# circuitofinal.net
KiCad netlist of a schematic drawn in EAGLE
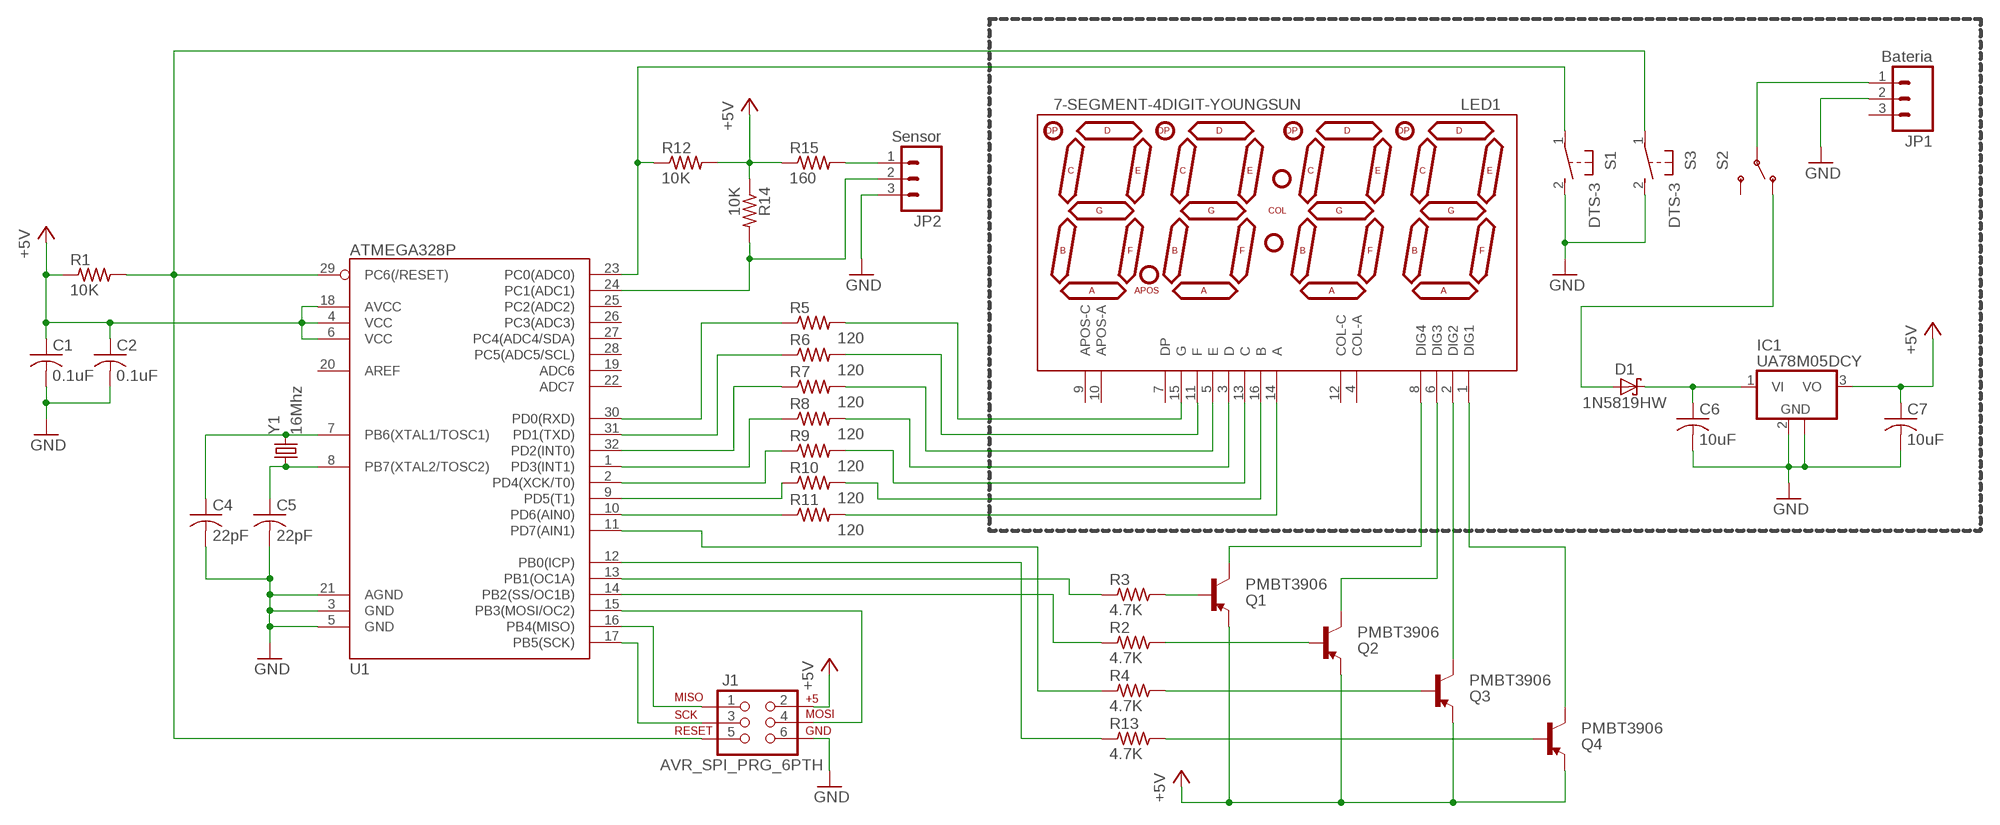
[diagram p0: schematic, sheet 1]

(export (version "E")
  (design (tool "Eeschema 10.0.6"))
  (components
    (comp (ref "C1")
      (value "0.1uF")
      (footprint "eagle-import:C0805")
      (libsource (lib "eagle-import") (part "C-USC0805"))
    )
    (comp (ref "C2")
      (value "0.1uF")
      (footprint "eagle-import:C0805")
      (libsource (lib "eagle-import") (part "C-USC0805"))
    )
    (comp (ref "C4")
      (value "22pF")
      (footprint "eagle-import:C1206")
      (libsource (lib "eagle-import") (part "C-USC1206"))
    )
    (comp (ref "C5")
      (value "22pF")
      (footprint "eagle-import:C1206")
      (libsource (lib "eagle-import") (part "C-USC1206"))
    )
    (comp (ref "C6")
      (value "10uF")
      (footprint "eagle-import:C1206")
      (libsource (lib "eagle-import") (part "C-USC1206"))
    )
    (comp (ref "C7")
      (value "10uF")
      (footprint "eagle-import:C1206")
      (libsource (lib "eagle-import") (part "C-USC1206"))
    )
    (comp (ref "D1")
      (value "1N5819HW")
      (footprint "eagle-import:SOD-123")
      (libsource (lib "eagle-import") (part "1N5819HW"))
    )
    (comp (ref "IC1")
      (value "UA78M05DCY")
      (footprint "eagle-import:SOT223")
      (libsource (lib "eagle-import") (part "UA78MDCY05"))
    )
    (comp (ref "J1")
      (value "AVR_SPI_PRG_6PTH")
      (footprint "eagle-import:2X3")
      (libsource (lib "eagle-import") (part "AVR_SPI_PRG_6PTH"))
    )
    (comp (ref "JP1")
      (value "Bateria")
      (footprint "eagle-import:JST-3-PTH")
      (libsource (lib "eagle-import") (part "M03JST-PTH"))
    )
    (comp (ref "JP2")
      (value "Sensor")
      (footprint "eagle-import:JST-3-PTH")
      (libsource (lib "eagle-import") (part "M03JST-PTH"))
    )
    (comp (ref "LED1")
      (value "7-SEGMENT-4DIGIT-YOUNGSUN")
      (footprint "eagle-import:7-SEGMENT-4DIGIT-YOUNGSUN")
      (libsource (lib "eagle-import") (part "7-SEGMENT-4DIGIT-YOUNGSUN"))
    )
    (comp (ref "Q1")
      (value "PMBT3906")
      (footprint "eagle-import:SOT23-3")
      (libsource (lib "eagle-import") (part "TRANSISTOR_PNPPMBT3906"))
    )
    (comp (ref "Q2")
      (value "PMBT3906")
      (footprint "eagle-import:SOT23-3")
      (libsource (lib "eagle-import") (part "TRANSISTOR_PNPPMBT3906"))
    )
    (comp (ref "Q3")
      (value "PMBT3906")
      (footprint "eagle-import:SOT23-3")
      (libsource (lib "eagle-import") (part "TRANSISTOR_PNPPMBT3906"))
    )
    (comp (ref "Q4")
      (value "PMBT3906")
      (footprint "eagle-import:SOT23-3")
      (libsource (lib "eagle-import") (part "TRANSISTOR_PNPPMBT3906"))
    )
    (comp (ref "R1")
      (value "10K")
      (footprint "eagle-import:R0805")
      (libsource (lib "eagle-import") (part "R-US_R0805"))
    )
    (comp (ref "R2")
      (value "4.7K")
      (footprint "eagle-import:R0805")
      (libsource (lib "eagle-import") (part "R-US_R0805"))
    )
    (comp (ref "R3")
      (value "4.7K")
      (footprint "eagle-import:R0805")
      (libsource (lib "eagle-import") (part "R-US_R0805"))
    )
    (comp (ref "R4")
      (value "4.7K")
      (footprint "eagle-import:R0805")
      (libsource (lib "eagle-import") (part "R-US_R0805"))
    )
    (comp (ref "R5")
      (value "120")
      (footprint "eagle-import:R0805")
      (libsource (lib "eagle-import") (part "R-US_R0805"))
    )
    (comp (ref "R6")
      (value "120")
      (footprint "eagle-import:R0805")
      (libsource (lib "eagle-import") (part "R-US_R0805"))
    )
    (comp (ref "R7")
      (value "120")
      (footprint "eagle-import:R0805")
      (libsource (lib "eagle-import") (part "R-US_R0805"))
    )
    (comp (ref "R8")
      (value "120")
      (footprint "eagle-import:R0805")
      (libsource (lib "eagle-import") (part "R-US_R0805"))
    )
    (comp (ref "R9")
      (value "120")
      (footprint "eagle-import:R0805")
      (libsource (lib "eagle-import") (part "R-US_R0805"))
    )
    (comp (ref "R10")
      (value "120")
      (footprint "eagle-import:R0805")
      (libsource (lib "eagle-import") (part "R-US_R0805"))
    )
    (comp (ref "R11")
      (value "120")
      (footprint "eagle-import:R0805")
      (libsource (lib "eagle-import") (part "R-US_R0805"))
    )
    (comp (ref "R12")
      (value "10K")
      (footprint "eagle-import:R0805")
      (libsource (lib "eagle-import") (part "R-US_R0805"))
    )
    (comp (ref "R13")
      (value "4.7K")
      (footprint "eagle-import:R0805")
      (libsource (lib "eagle-import") (part "R-US_R0805"))
    )
    (comp (ref "R14")
      (value "10K")
      (footprint "eagle-import:R0805")
      (libsource (lib "eagle-import") (part "R-US_R0805"))
    )
    (comp (ref "R15")
      (value "160")
      (footprint "eagle-import:R1206")
      (libsource (lib "eagle-import") (part "R-US_R1206"))
    )
    (comp (ref "S1")
      (value "DTS-3")
      (footprint "eagle-import:DTS-3")
      (libsource (lib "eagle-import") (part "DTS-3"))
    )
    (comp (ref "S2")
      (value "SWITCH-SPDTPTH")
      (footprint "eagle-import:SWITCH-SPDT")
      (libsource (lib "eagle-import") (part "SWITCH-SPDTPTH"))
    )
    (comp (ref "S3")
      (value "DTS-3")
      (footprint "eagle-import:DTS-3")
      (libsource (lib "eagle-import") (part "DTS-3"))
    )
    (comp (ref "U1")
      (value "ATMEGA328P")
      (footprint "eagle-import:TQFP32-08")
      (libsource (lib "eagle-import") (part "ATMEGA328_SMT"))
    )
    (comp (ref "Y1")
      (value "16Mhz")
      (footprint "eagle-import:HC49US")
      (libsource (lib "eagle-import") (part "CRYSTALHC49US"))
    )
  )
  (nets
    (net (code "1") (name "+5V") (class "Default")
      (node (ref "C1") (pin "1") (pinfunction "1_1") (pintype "passive"))
      (node (ref "C2") (pin "1") (pinfunction "1_1") (pintype "passive"))
      (node (ref "C7") (pin "1") (pinfunction "1_1") (pintype "passive"))
      (node (ref "IC1") (pin "3") (pinfunction "VO_3") (pintype "passive"))
      (node (ref "J1") (pin "2") (pinfunction "2_2") (pintype "passive"))
      (node (ref "Q1") (pin "2") (pinfunction "E_2") (pintype "passive"))
      (node (ref "Q2") (pin "2") (pinfunction "E_2") (pintype "passive"))
      (node (ref "Q3") (pin "2") (pinfunction "E_2") (pintype "passive"))
      (node (ref "Q4") (pin "2") (pinfunction "E_2") (pintype "passive"))
      (node (ref "R1") (pin "1") (pinfunction "1_1") (pintype "passive"))
      (node (ref "R12") (pin "2") (pinfunction "2_2") (pintype "passive"))
      (node (ref "R14") (pin "1") (pinfunction "1_1") (pintype "passive"))
      (node (ref "R15") (pin "1") (pinfunction "1_1") (pintype "passive"))
      (node (ref "U1") (pin "18") (pinfunction "AVCC_18") (pintype "bidirectional"))
      (node (ref "U1") (pin "4") (pinfunction "VCC_4") (pintype "bidirectional"))
      (node (ref "U1") (pin "6") (pinfunction "VCC_6") (pintype "bidirectional"))
    )
    (net (code "2") (name "GND") (class "Default")
      (node (ref "C1") (pin "2") (pinfunction "2_2") (pintype "passive"))
      (node (ref "C2") (pin "2") (pinfunction "2_2") (pintype "passive"))
      (node (ref "C4") (pin "2") (pinfunction "2_2") (pintype "passive"))
      (node (ref "C5") (pin "2") (pinfunction "2_2") (pintype "passive"))
      (node (ref "C6") (pin "2") (pinfunction "2_2") (pintype "passive"))
      (node (ref "C7") (pin "2") (pinfunction "2_2") (pintype "passive"))
      (node (ref "IC1") (pin "2") (pinfunction "GND_2") (pintype "passive"))
      (node (ref "IC1") (pin "4") (pinfunction "GND_4") (pintype "passive"))
      (node (ref "J1") (pin "6") (pinfunction "6_6") (pintype "passive"))
      (node (ref "JP1") (pin "2") (pinfunction "2_2") (pintype "passive"))
      (node (ref "JP2") (pin "3") (pinfunction "3_3") (pintype "passive"))
      (node (ref "S1") (pin "2") (pinfunction "2_2") (pintype "passive"))
      (node (ref "S3") (pin "2") (pinfunction "2_2") (pintype "passive"))
      (node (ref "U1") (pin "21") (pinfunction "AGND_21") (pintype "bidirectional"))
      (node (ref "U1") (pin "3") (pinfunction "GND_3") (pintype "bidirectional"))
      (node (ref "U1") (pin "5") (pinfunction "GND_5") (pintype "bidirectional"))
    )
    (net (code "3") (name "Net-(IC1-VI)") (class "Default")
      (node (ref "C6") (pin "1") (pinfunction "1_1") (pintype "passive"))
      (node (ref "D1") (pin "C") (pinfunction "C_C") (pintype "passive"))
      (node (ref "IC1") (pin "1") (pinfunction "VI_1") (pintype "input"))
    )
    (net (code "4") (name "Net-(JP2-Pad1)") (class "Default")
      (node (ref "JP2") (pin "1") (pinfunction "1_1") (pintype "passive"))
      (node (ref "R15") (pin "2") (pinfunction "2_2") (pintype "passive"))
    )
    (net (code "5") (name "Net-(LED1-A)") (class "Default")
      (node (ref "LED1") (pin "14") (pinfunction "A_14") (pintype "bidirectional"))
      (node (ref "R11") (pin "2") (pinfunction "2_2") (pintype "passive"))
    )
    (net (code "6") (name "Net-(LED1-B)") (class "Default")
      (node (ref "LED1") (pin "16") (pinfunction "B_16") (pintype "bidirectional"))
      (node (ref "R10") (pin "2") (pinfunction "2_2") (pintype "passive"))
    )
    (net (code "7") (name "Net-(LED1-C)") (class "Default")
      (node (ref "LED1") (pin "13") (pinfunction "C_13") (pintype "bidirectional"))
      (node (ref "R9") (pin "2") (pinfunction "2_2") (pintype "passive"))
    )
    (net (code "8") (name "Net-(LED1-D)") (class "Default")
      (node (ref "LED1") (pin "3") (pinfunction "D_3") (pintype "bidirectional"))
      (node (ref "R8") (pin "2") (pinfunction "2_2") (pintype "passive"))
    )
    (net (code "9") (name "Net-(LED1-DIG1)") (class "Default")
      (node (ref "LED1") (pin "1") (pinfunction "DIG1_1") (pintype "bidirectional"))
      (node (ref "Q4") (pin "3") (pinfunction "C_3") (pintype "passive"))
    )
    (net (code "10") (name "Net-(LED1-DIG2)") (class "Default")
      (node (ref "LED1") (pin "2") (pinfunction "DIG2_2") (pintype "bidirectional"))
      (node (ref "Q3") (pin "3") (pinfunction "C_3") (pintype "passive"))
    )
    (net (code "11") (name "Net-(LED1-DIG3)") (class "Default")
      (node (ref "LED1") (pin "6") (pinfunction "DIG3_6") (pintype "bidirectional"))
      (node (ref "Q2") (pin "3") (pinfunction "C_3") (pintype "passive"))
    )
    (net (code "12") (name "Net-(LED1-DIG4)") (class "Default")
      (node (ref "LED1") (pin "8") (pinfunction "DIG4_8") (pintype "bidirectional"))
      (node (ref "Q1") (pin "3") (pinfunction "C_3") (pintype "passive"))
    )
    (net (code "13") (name "Net-(LED1-E)") (class "Default")
      (node (ref "LED1") (pin "5") (pinfunction "E_5") (pintype "bidirectional"))
      (node (ref "R7") (pin "2") (pinfunction "2_2") (pintype "passive"))
    )
    (net (code "14") (name "Net-(LED1-F)") (class "Default")
      (node (ref "LED1") (pin "11") (pinfunction "F_11") (pintype "bidirectional"))
      (node (ref "R6") (pin "2") (pinfunction "2_2") (pintype "passive"))
    )
    (net (code "15") (name "Net-(LED1-G)") (class "Default")
      (node (ref "LED1") (pin "15") (pinfunction "G_15") (pintype "bidirectional"))
      (node (ref "R5") (pin "2") (pinfunction "2_2") (pintype "passive"))
    )
    (net (code "16") (name "Net-(Q1-B)") (class "Default")
      (node (ref "Q1") (pin "1") (pinfunction "B_1") (pintype "passive"))
      (node (ref "R3") (pin "2") (pinfunction "2_2") (pintype "passive"))
    )
    (net (code "17") (name "Net-(Q2-B)") (class "Default")
      (node (ref "Q2") (pin "1") (pinfunction "B_1") (pintype "passive"))
      (node (ref "R2") (pin "2") (pinfunction "2_2") (pintype "passive"))
    )
    (net (code "18") (name "Net-(Q3-B)") (class "Default")
      (node (ref "Q3") (pin "1") (pinfunction "B_1") (pintype "passive"))
      (node (ref "R4") (pin "2") (pinfunction "2_2") (pintype "passive"))
    )
    (net (code "19") (name "Net-(Q4-B)") (class "Default")
      (node (ref "Q4") (pin "1") (pinfunction "B_1") (pintype "passive"))
      (node (ref "R13") (pin "2") (pinfunction "2_2") (pintype "passive"))
    )
    (net (code "20") (name "Net-(S2-O)") (class "Default")
      (node (ref "D1") (pin "A") (pinfunction "A_A") (pintype "passive"))
      (node (ref "S2") (pin "1") (pinfunction "O_1") (pintype "passive"))
    )
    (net (code "21") (name "Net-(S2-P)") (class "Default")
      (node (ref "JP1") (pin "1") (pinfunction "1_1") (pintype "passive"))
      (node (ref "S2") (pin "2") (pinfunction "P_2") (pintype "passive"))
    )
    (net (code "22") (name "Net-(U1-PB0(ICP))") (class "Default")
      (node (ref "R13") (pin "1") (pinfunction "1_1") (pintype "passive"))
      (node (ref "U1") (pin "12") (pinfunction "PB0(ICP)_12") (pintype "bidirectional"))
    )
    (net (code "23") (name "Net-(U1-PB1(OC1A))") (class "Default")
      (node (ref "R3") (pin "1") (pinfunction "1_1") (pintype "passive"))
      (node (ref "U1") (pin "13") (pinfunction "PB1(OC1A)_13") (pintype "bidirectional"))
    )
    (net (code "24") (name "Net-(U1-PB2(SS{slash}OC1B))") (class "Default")
      (node (ref "R2") (pin "1") (pinfunction "1_1") (pintype "passive"))
      (node (ref "U1") (pin "14") (pinfunction "PB2(SS/OC1B)_14") (pintype "bidirectional"))
    )
    (net (code "25") (name "Net-(U1-PB3(MOSI{slash}OC2))") (class "Default")
      (node (ref "J1") (pin "4") (pinfunction "4_4") (pintype "passive"))
      (node (ref "U1") (pin "15") (pinfunction "PB3(MOSI/OC2)_15") (pintype "bidirectional"))
    )
    (net (code "26") (name "Net-(U1-PB4(MISO))") (class "Default")
      (node (ref "J1") (pin "1") (pinfunction "1_1") (pintype "passive"))
      (node (ref "U1") (pin "16") (pinfunction "PB4(MISO)_16") (pintype "bidirectional"))
    )
    (net (code "27") (name "Net-(U1-PB5(SCK))") (class "Default")
      (node (ref "J1") (pin "3") (pinfunction "3_3") (pintype "passive"))
      (node (ref "U1") (pin "17") (pinfunction "PB5(SCK)_17") (pintype "bidirectional"))
    )
    (net (code "28") (name "Net-(U1-PB6(XTAL1{slash}TOSC1))") (class "Default")
      (node (ref "C4") (pin "1") (pinfunction "1_1") (pintype "passive"))
      (node (ref "U1") (pin "7") (pinfunction "PB6(XTAL1/TOSC1)_7") (pintype "bidirectional"))
      (node (ref "Y1") (pin "2") (pinfunction "2_2") (pintype "passive"))
    )
    (net (code "29") (name "Net-(U1-PB7(XTAL2{slash}TOSC2))") (class "Default")
      (node (ref "C5") (pin "1") (pinfunction "1_1") (pintype "passive"))
      (node (ref "U1") (pin "8") (pinfunction "PB7(XTAL2/TOSC2)_8") (pintype "bidirectional"))
      (node (ref "Y1") (pin "1") (pinfunction "1_1") (pintype "passive"))
    )
    (net (code "30") (name "Net-(U1-PC0(ADC0))") (class "Default")
      (node (ref "R12") (pin "1") (pinfunction "1_1") (pintype "passive"))
      (node (ref "S1") (pin "1") (pinfunction "1_1") (pintype "passive"))
      (node (ref "U1") (pin "23") (pinfunction "PC0(ADC0)_23") (pintype "bidirectional"))
    )
    (net (code "31") (name "Net-(U1-PC1(ADC1))") (class "Default")
      (node (ref "JP2") (pin "2") (pinfunction "2_2") (pintype "passive"))
      (node (ref "R14") (pin "2") (pinfunction "2_2") (pintype "passive"))
      (node (ref "U1") (pin "24") (pinfunction "PC1(ADC1)_24") (pintype "bidirectional"))
    )
    (net (code "32") (name "Net-(U1-PC6({slash}RESET))") (class "Default")
      (node (ref "J1") (pin "5") (pinfunction "5_5") (pintype "passive"))
      (node (ref "R1") (pin "2") (pinfunction "2_2") (pintype "passive"))
      (node (ref "S3") (pin "1") (pinfunction "1_1") (pintype "passive"))
      (node (ref "U1") (pin "29") (pinfunction "PC6(/RESET)_29") (pintype "bidirectional"))
    )
    (net (code "33") (name "Net-(U1-PD0(RXD))") (class "Default")
      (node (ref "R5") (pin "1") (pinfunction "1_1") (pintype "passive"))
      (node (ref "U1") (pin "30") (pinfunction "PD0(RXD)_30") (pintype "bidirectional"))
    )
    (net (code "34") (name "Net-(U1-PD1(TXD))") (class "Default")
      (node (ref "R6") (pin "1") (pinfunction "1_1") (pintype "passive"))
      (node (ref "U1") (pin "31") (pinfunction "PD1(TXD)_31") (pintype "bidirectional"))
    )
    (net (code "35") (name "Net-(U1-PD2(INT0))") (class "Default")
      (node (ref "R7") (pin "1") (pinfunction "1_1") (pintype "passive"))
      (node (ref "U1") (pin "32") (pinfunction "PD2(INT0)_32") (pintype "bidirectional"))
    )
    (net (code "36") (name "Net-(U1-PD3(INT1))") (class "Default")
      (node (ref "R8") (pin "1") (pinfunction "1_1") (pintype "passive"))
      (node (ref "U1") (pin "1") (pinfunction "PD3(INT1)_1") (pintype "bidirectional"))
    )
    (net (code "37") (name "Net-(U1-PD4(XCK{slash}T0))") (class "Default")
      (node (ref "R9") (pin "1") (pinfunction "1_1") (pintype "passive"))
      (node (ref "U1") (pin "2") (pinfunction "PD4(XCK/T0)_2") (pintype "bidirectional"))
    )
    (net (code "38") (name "Net-(U1-PD5(T1))") (class "Default")
      (node (ref "R10") (pin "1") (pinfunction "1_1") (pintype "passive"))
      (node (ref "U1") (pin "9") (pinfunction "PD5(T1)_9") (pintype "bidirectional"))
    )
    (net (code "39") (name "Net-(U1-PD6(AIN0))") (class "Default")
      (node (ref "R11") (pin "1") (pinfunction "1_1") (pintype "passive"))
      (node (ref "U1") (pin "10") (pinfunction "PD6(AIN0)_10") (pintype "bidirectional"))
    )
    (net (code "40") (name "Net-(U1-PD7(AIN1))") (class "Default")
      (node (ref "R4") (pin "1") (pinfunction "1_1") (pintype "passive"))
      (node (ref "U1") (pin "11") (pinfunction "PD7(AIN1)_11") (pintype "bidirectional"))
    )
    (net (code "41") (name "unconnected-(JP1-Pad3)") (class "Default")
      (node (ref "JP1") (pin "3") (pinfunction "3_3") (pintype "passive"))
    )
    (net (code "42") (name "unconnected-(LED1-APOS-A-Pad10)") (class "Default")
      (node (ref "LED1") (pin "10") (pinfunction "APOS-A_10") (pintype "bidirectional"))
    )
    (net (code "43") (name "unconnected-(LED1-APOS-C-Pad9)") (class "Default")
      (node (ref "LED1") (pin "9") (pinfunction "APOS-C_9") (pintype "bidirectional"))
    )
    (net (code "44") (name "unconnected-(LED1-COL-A-Pad4)") (class "Default")
      (node (ref "LED1") (pin "4") (pinfunction "COL-A_4") (pintype "bidirectional"))
    )
    (net (code "45") (name "unconnected-(LED1-COL-C-Pad12)") (class "Default")
      (node (ref "LED1") (pin "12") (pinfunction "COL-C_12") (pintype "bidirectional"))
    )
    (net (code "46") (name "unconnected-(LED1-DP-Pad7)") (class "Default")
      (node (ref "LED1") (pin "7") (pinfunction "DP_7") (pintype "bidirectional"))
    )
    (net (code "47") (name "unconnected-(S2-S-Pad3)") (class "Default")
      (node (ref "S2") (pin "3") (pinfunction "S_3") (pintype "passive"))
    )
    (net (code "48") (name "unconnected-(U1-ADC6-Pad19)") (class "Default")
      (node (ref "U1") (pin "19") (pinfunction "ADC6_19") (pintype "bidirectional"))
    )
    (net (code "49") (name "unconnected-(U1-ADC7-Pad22)") (class "Default")
      (node (ref "U1") (pin "22") (pinfunction "ADC7_22") (pintype "bidirectional"))
    )
    (net (code "50") (name "unconnected-(U1-AREF-Pad20)") (class "Default")
      (node (ref "U1") (pin "20") (pinfunction "AREF_20") (pintype "bidirectional"))
    )
    (net (code "51") (name "unconnected-(U1-PC2(ADC2)-Pad25)") (class "Default")
      (node (ref "U1") (pin "25") (pinfunction "PC2(ADC2)_25") (pintype "bidirectional"))
    )
    (net (code "52") (name "unconnected-(U1-PC3(ADC3)-Pad26)") (class "Default")
      (node (ref "U1") (pin "26") (pinfunction "PC3(ADC3)_26") (pintype "bidirectional"))
    )
    (net (code "53") (name "unconnected-(U1-PC4(ADC4{slash}SDA)-Pad27)") (class "Default")
      (node (ref "U1") (pin "27") (pinfunction "PC4(ADC4/SDA)_27") (pintype "bidirectional"))
    )
    (net (code "54") (name "unconnected-(U1-PC5(ADC5{slash}SCL)-Pad28)") (class "Default")
      (node (ref "U1") (pin "28") (pinfunction "PC5(ADC5/SCL)_28") (pintype "bidirectional"))
    )
  )
)
